# Robotic_Finger_Sensor.net
KiCad netlist of a schematic drawn in EAGLE
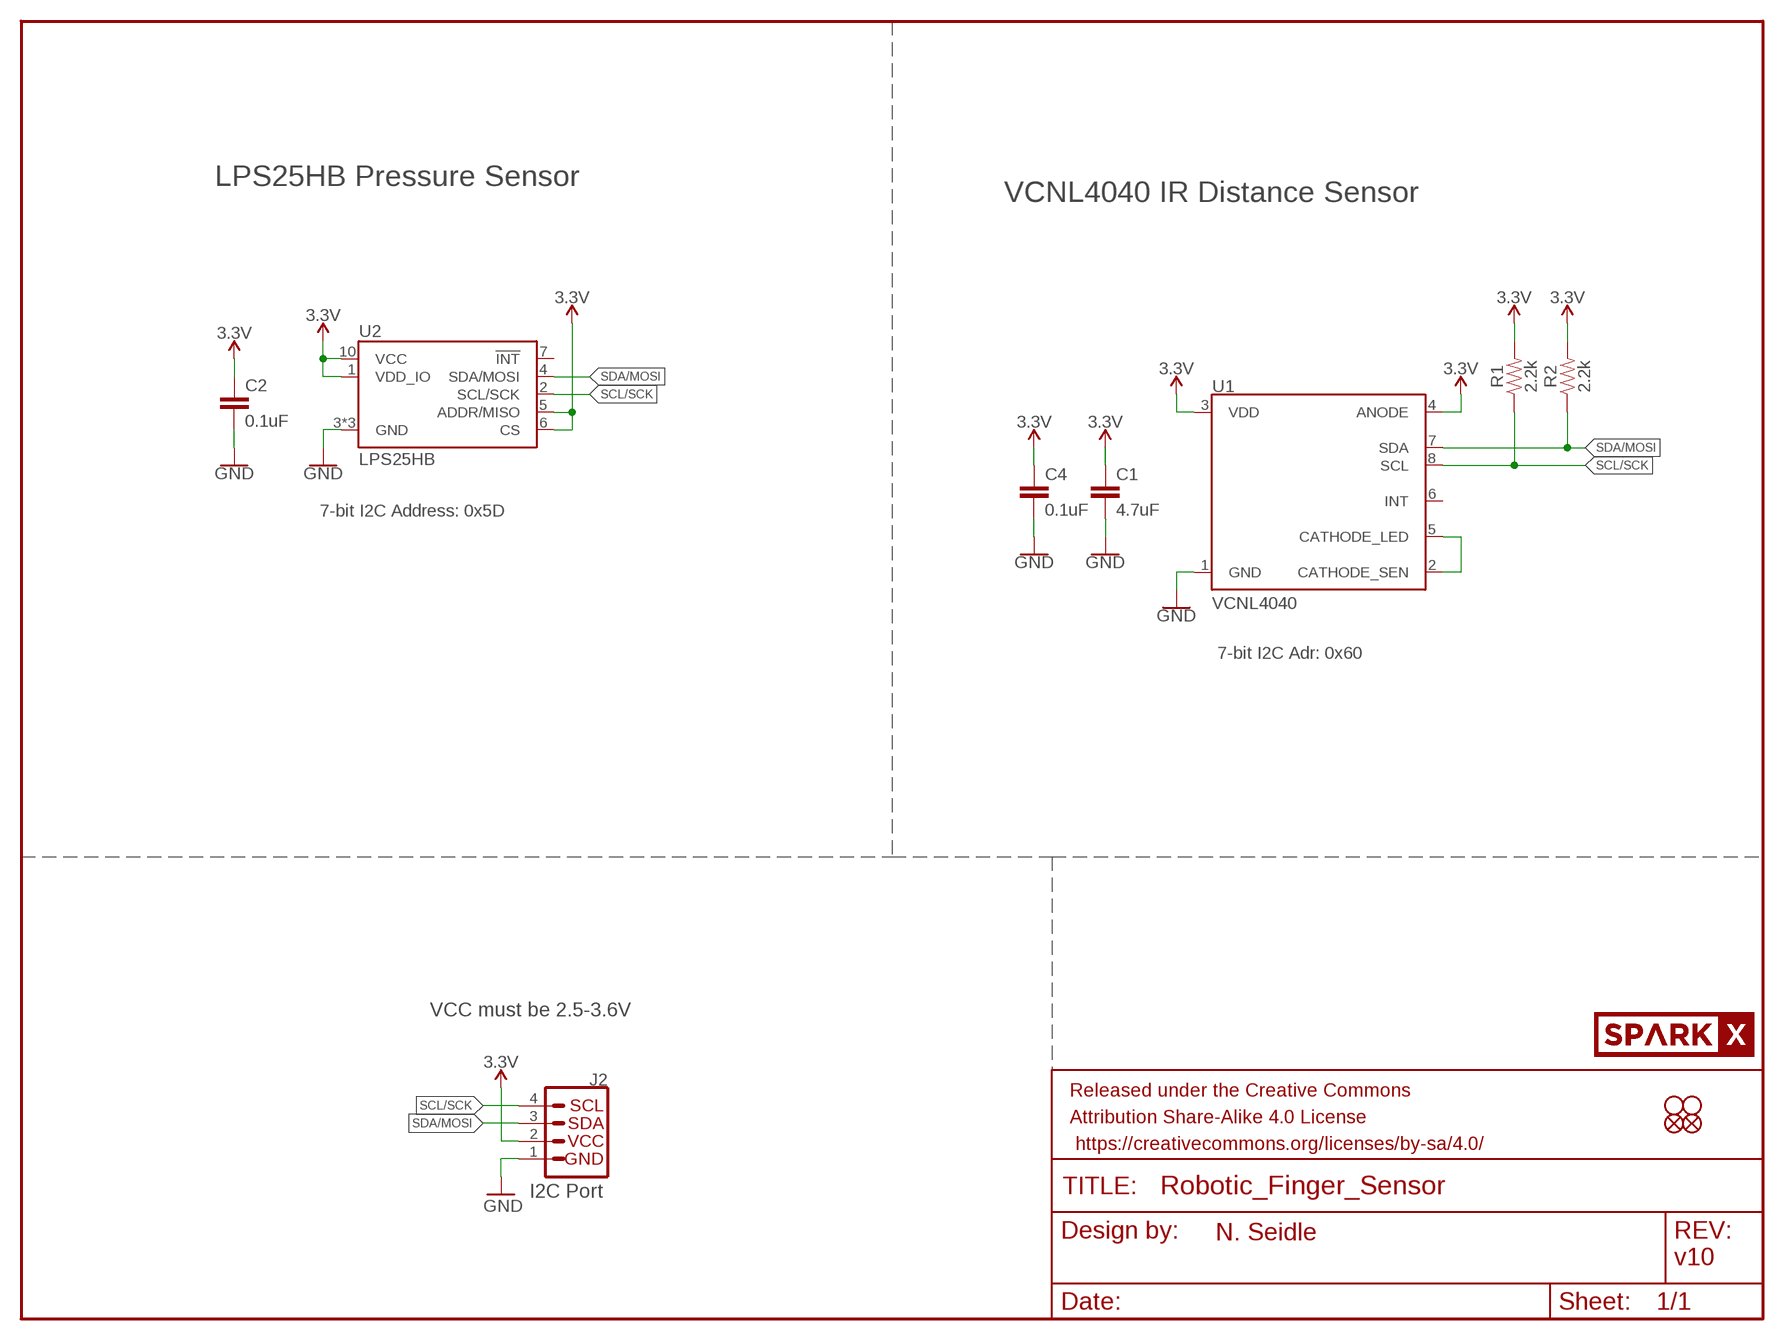
[diagram p0: schematic, sheet 1]

(export (version "E")
  (design (tool "Eeschema 10.0.6"))
  (components
    (comp (ref "C1")
      (value "4.7uF")
      (footprint "eagle-import:0603")
      (libsource (lib "eagle-import") (part "4.7UF0603"))
    )
    (comp (ref "C2")
      (value "0.1uF")
      (footprint "eagle-import:0603")
      (libsource (lib "eagle-import") (part "0.1UF-0603-25V-(+80/-20%)"))
    )
    (comp (ref "C4")
      (value "0.1uF")
      (footprint "eagle-import:0603")
      (libsource (lib "eagle-import") (part "0.1UF-0603-25V-(+80/-20%)"))
    )
    (comp (ref "FD1")
      (value "FIDUCIALUFIDUCIAL")
      (footprint "eagle-import:FIDUCIAL-MICRO")
      (libsource (lib "eagle-import") (part "FIDUCIALUFIDUCIAL"))
    )
    (comp (ref "FD2")
      (value "FIDUCIALUFIDUCIAL")
      (footprint "eagle-import:FIDUCIAL-MICRO")
      (libsource (lib "eagle-import") (part "FIDUCIALUFIDUCIAL"))
    )
    (comp (ref "FRAME2")
      (value "FRAME-LETTER")
      (footprint "eagle-import:CREATIVE_COMMONS")
      (libsource (lib "eagle-import") (part "FRAME-LETTER"))
    )
    (comp (ref "J2")
      (value "I2C_STANDARDJS-1MM")
      (footprint "eagle-import:1X04_1MM_RA")
      (libsource (lib "eagle-import") (part "I2C_STANDARDJS-1MM"))
    )
    (comp (ref "R1")
      (value "2.2k")
      (footprint "eagle-import:0603")
      (libsource (lib "eagle-import") (part "2.2KOHM-0603-1/10W-1%"))
    )
    (comp (ref "R2")
      (value "2.2k")
      (footprint "eagle-import:0603")
      (libsource (lib "eagle-import") (part "2.2KOHM-0603-1/10W-1%"))
    )
    (comp (ref "U$2")
      (value "SPARKX-LOGO3")
      (footprint "eagle-import:SPARKX-SMALL")
      (libsource (lib "eagle-import") (part "SPARKX-LOGO3"))
    )
    (comp (ref "U$3")
      (value "STAND-OFF")
      (footprint "eagle-import:STAND-OFF-#2")
      (libsource (lib "eagle-import") (part "STAND-OFF"))
    )
    (comp (ref "U$4")
      (value "STAND-OFF")
      (footprint "eagle-import:STAND-OFF-#2")
      (libsource (lib "eagle-import") (part "STAND-OFF"))
    )
    (comp (ref "U1")
      (value "VCNL4040")
      (footprint "eagle-import:VCNL4040")
      (libsource (lib "eagle-import") (part "VCNL4040"))
    )
    (comp (ref "U2")
      (value "LPS25HB")
      (footprint "eagle-import:LPS25HB")
      (libsource (lib "eagle-import") (part "LPS25HB"))
    )
  )
  (nets
    (net (code "1") (name "3.3V") (class "Default")
      (node (ref "C1") (pin "1") (pinfunction "1_1") (pintype "passive"))
      (node (ref "C2") (pin "1") (pinfunction "1_1") (pintype "passive"))
      (node (ref "C4") (pin "1") (pinfunction "1_1") (pintype "passive"))
      (node (ref "J2") (pin "2") (pinfunction "VCC_2") (pintype "power_in"))
      (node (ref "R1") (pin "2") (pinfunction "2_2") (pintype "passive"))
      (node (ref "R2") (pin "2") (pinfunction "2_2") (pintype "passive"))
      (node (ref "U1") (pin "3") (pinfunction "VDD_3") (pintype "bidirectional"))
      (node (ref "U1") (pin "4") (pinfunction "ANODE_4") (pintype "bidirectional"))
      (node (ref "U2") (pin "1") (pinfunction "VDD_IO_1") (pintype "bidirectional"))
      (node (ref "U2") (pin "10") (pinfunction "VCC_10") (pintype "bidirectional"))
      (node (ref "U2") (pin "5") (pinfunction "ADDR/MISO_5") (pintype "bidirectional"))
      (node (ref "U2") (pin "6") (pinfunction "CS_6") (pintype "bidirectional"))
    )
    (net (code "2") (name "GND") (class "Default")
      (node (ref "C1") (pin "2") (pinfunction "2_2") (pintype "passive"))
      (node (ref "C2") (pin "2") (pinfunction "2_2") (pintype "passive"))
      (node (ref "C4") (pin "2") (pinfunction "2_2") (pintype "passive"))
      (node (ref "J2") (pin "1") (pinfunction "GND_1") (pintype "power_in"))
      (node (ref "U1") (pin "1") (pinfunction "GND_1") (pintype "bidirectional"))
      (node (ref "U2") (pin "3") (pinfunction "GND_3") (pintype "bidirectional"))
      (node (ref "U2") (pin "8") (pinfunction "GND_8") (pintype "bidirectional"))
      (node (ref "U2") (pin "9") (pinfunction "GND_9") (pintype "bidirectional"))
    )
    (net (code "3") (name "Net-(U1-CATHODE_LED)") (class "Default")
      (node (ref "U1") (pin "2") (pinfunction "CATHODE_SEN_2") (pintype "bidirectional"))
      (node (ref "U1") (pin "5") (pinfunction "CATHODE_LED_5") (pintype "bidirectional"))
    )
    (net (code "4") (name "SCL{slash}SCK") (class "Default")
      (node (ref "J2") (pin "4") (pinfunction "SCL_4") (pintype "passive"))
      (node (ref "R1") (pin "1") (pinfunction "1_1") (pintype "passive"))
      (node (ref "U1") (pin "8") (pinfunction "SCL_8") (pintype "bidirectional"))
      (node (ref "U2") (pin "2") (pinfunction "SCL/SCK_2") (pintype "bidirectional"))
    )
    (net (code "5") (name "SDA{slash}MOSI") (class "Default")
      (node (ref "J2") (pin "3") (pinfunction "SDA_3") (pintype "passive"))
      (node (ref "R2") (pin "1") (pinfunction "1_1") (pintype "passive"))
      (node (ref "U1") (pin "7") (pinfunction "SDA_7") (pintype "bidirectional"))
      (node (ref "U2") (pin "4") (pinfunction "SDA/MOSI_4") (pintype "bidirectional"))
    )
    (net (code "6") (name "unconnected-(U1-INT-Pad6)") (class "Default")
      (node (ref "U1") (pin "6") (pinfunction "INT_6") (pintype "bidirectional"))
    )
    (net (code "7") (name "unconnected-(U2-~{INT}-Pad7)") (class "Default")
      (node (ref "U2") (pin "7") (pinfunction "~{INT}_7") (pintype "bidirectional"))
    )
  )
)
